# AST2001.net
KiCad netlist of a schematic drawn in EAGLE
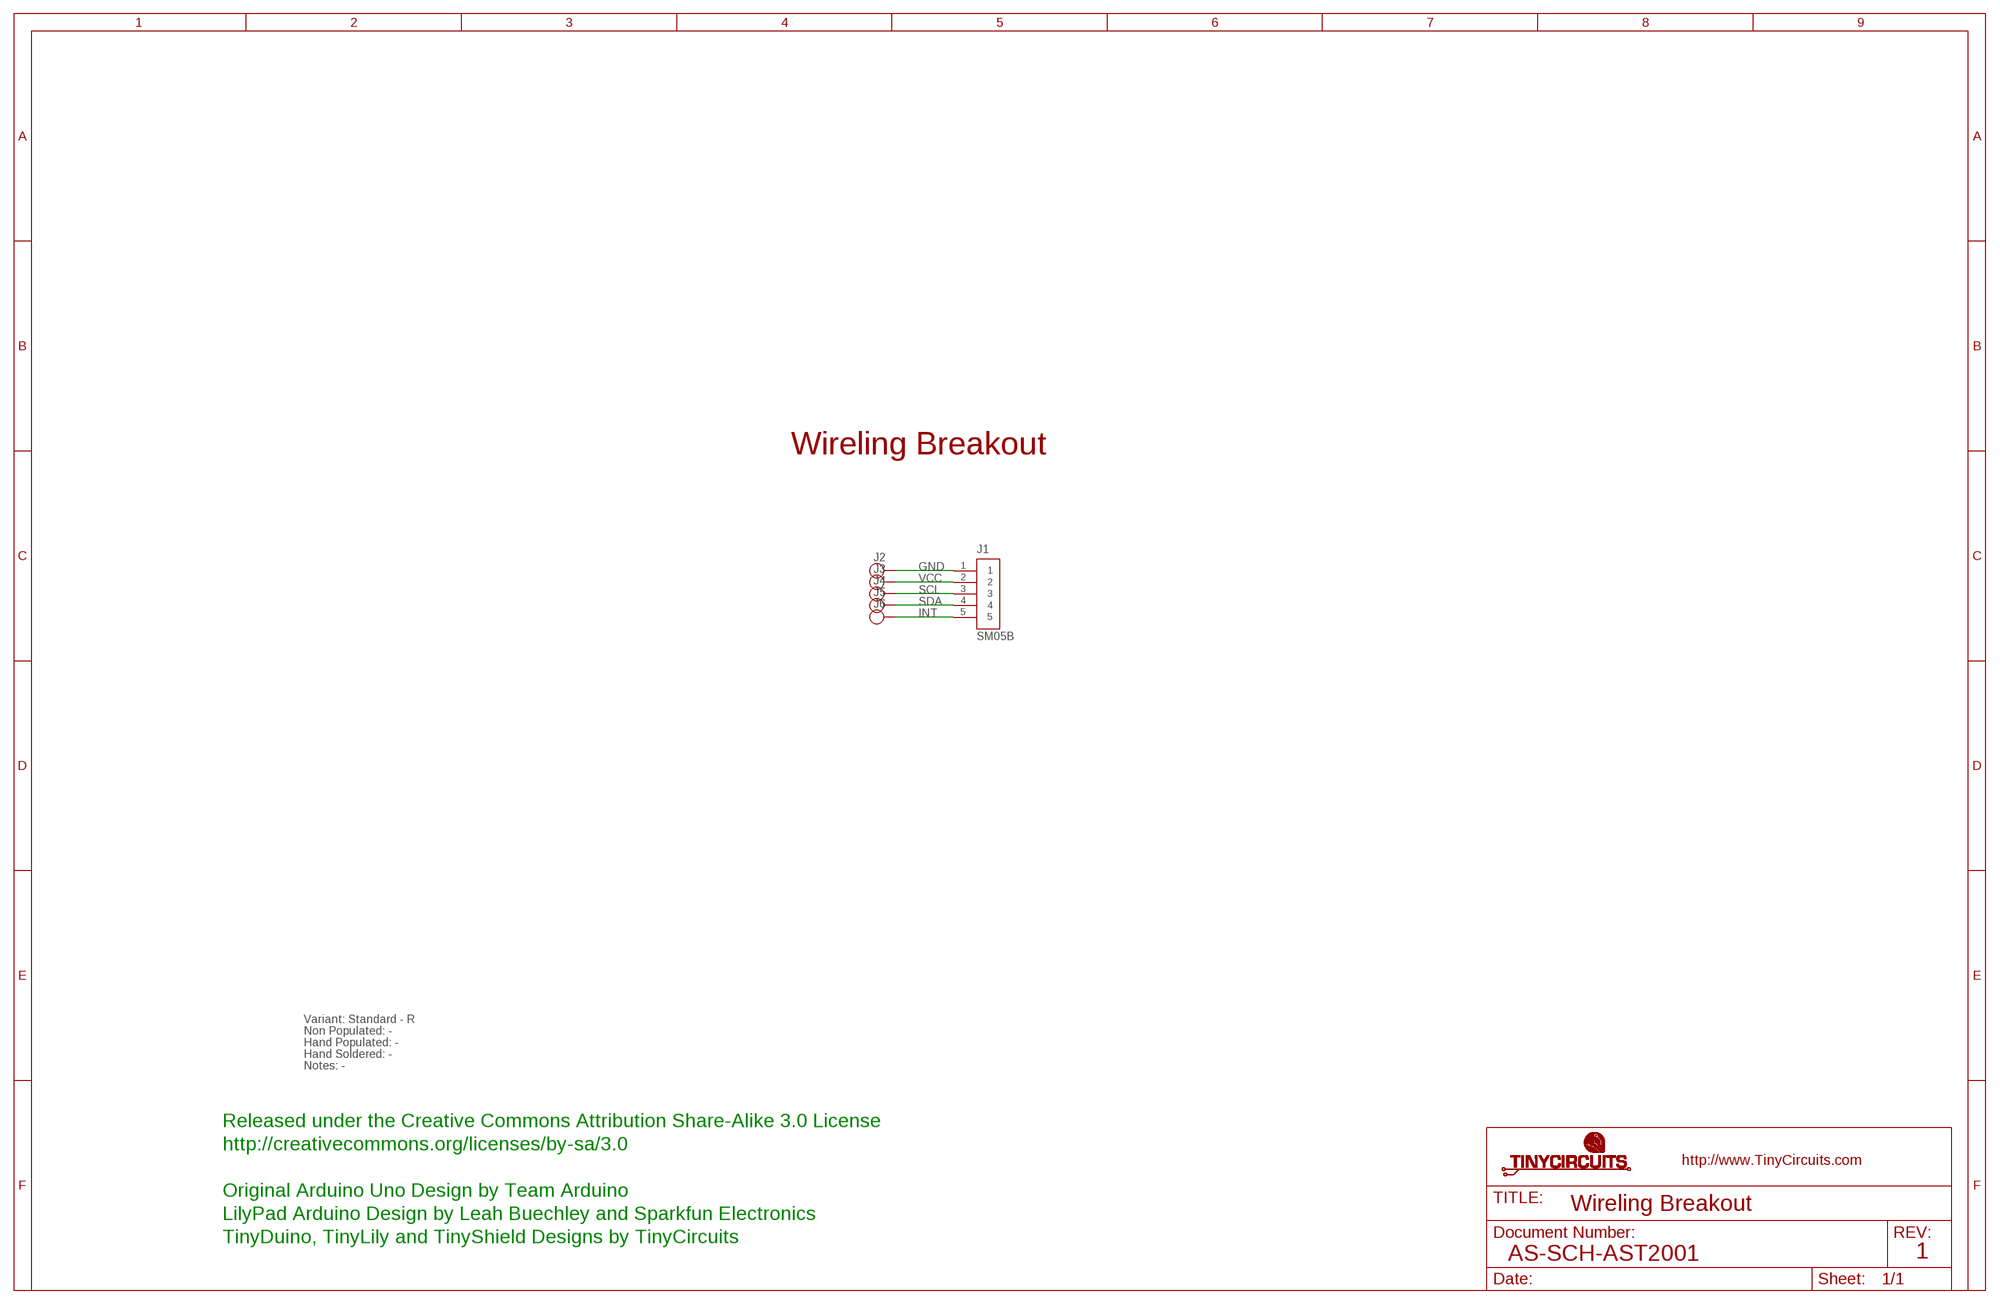
[diagram p0: schematic, sheet 1]

(export (version "E")
  (design (tool "Eeschema 10.0.6"))
  (components
    (comp (ref "J1")
      (value "SM05B")
      (footprint "eagle-import:JST_SH_5X1_EDGE")
      (fields (field (name "PARTNO") "AS-ITM-00340"))
      (libsource (lib "eagle-import") (part "AS-ITM-00340EDGE"))
    )
    (comp (ref "J2")
      (value "PIN_1X.1\"1")
      (footprint "eagle-import:1X.1__2")
      (libsource (lib "eagle-import") (part "PIN_1X.1{dblquote}1"))
    )
    (comp (ref "J3")
      (value "PIN_1X.1\"1")
      (footprint "eagle-import:1X.1__2")
      (libsource (lib "eagle-import") (part "PIN_1X.1{dblquote}1"))
    )
    (comp (ref "J4")
      (value "PIN_1X.1\"1")
      (footprint "eagle-import:1X.1__2")
      (libsource (lib "eagle-import") (part "PIN_1X.1{dblquote}1"))
    )
    (comp (ref "J5")
      (value "PIN_1X.1\"1")
      (footprint "eagle-import:1X.1__2")
      (libsource (lib "eagle-import") (part "PIN_1X.1{dblquote}1"))
    )
    (comp (ref "J6")
      (value "PIN_1X.1\"1")
      (footprint "eagle-import:1X.1__2")
      (libsource (lib "eagle-import") (part "PIN_1X.1{dblquote}1"))
    )
  )
  (nets
    (net (code "1") (name "/GND") (class "Default")
      (node (ref "J1") (pin "1") (pinfunction "1_1") (pintype "bidirectional"))
      (node (ref "J2") (pin "1") (pinfunction "1_1") (pintype "bidirectional"))
    )
    (net (code "2") (name "/INT") (class "Default")
      (node (ref "J1") (pin "5") (pinfunction "5_5") (pintype "bidirectional"))
      (node (ref "J6") (pin "1") (pinfunction "1_1") (pintype "bidirectional"))
    )
    (net (code "3") (name "/SCL") (class "Default")
      (node (ref "J1") (pin "3") (pinfunction "3_3") (pintype "bidirectional"))
      (node (ref "J4") (pin "1") (pinfunction "1_1") (pintype "bidirectional"))
    )
    (net (code "4") (name "/SDA") (class "Default")
      (node (ref "J1") (pin "4") (pinfunction "4_4") (pintype "bidirectional"))
      (node (ref "J5") (pin "1") (pinfunction "1_1") (pintype "bidirectional"))
    )
    (net (code "5") (name "/VCC") (class "Default")
      (node (ref "J1") (pin "2") (pinfunction "2_2") (pintype "bidirectional"))
      (node (ref "J3") (pin "1") (pinfunction "1_1") (pintype "bidirectional"))
    )
  )
)
